# equilizerShield.net
KiCad netlist of a schematic drawn in EAGLE
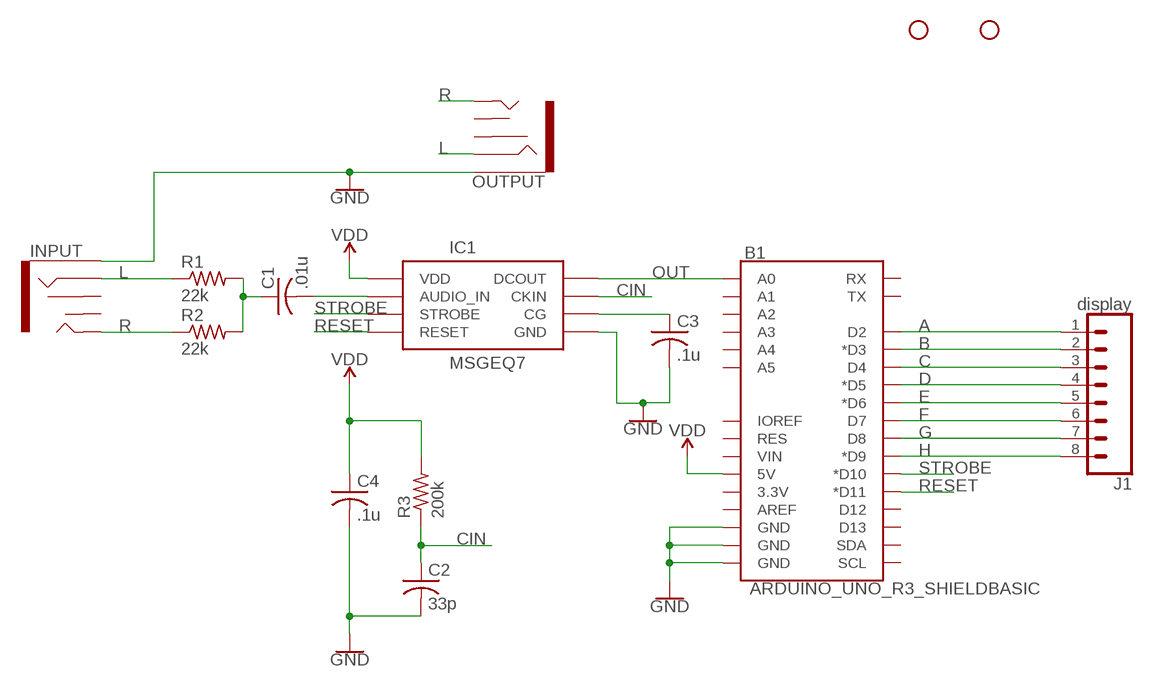
[diagram p0: schematic, sheet 1]

(export (version "E")
  (design (tool "Eeschema 10.0.6"))
  (components
    (comp (ref "B1")
      (value "ARDUINO_UNO_R3_SHIELDBASIC")
      (footprint "eagle-import:UNO_R3_SHIELD")
      (libsource (lib "eagle-import") (part "ARDUINO_UNO_R3_SHIELDBASIC"))
    )
    (comp (ref "C1")
      (value ".01u")
      (footprint "eagle-import:C0805")
      (libsource (lib "eagle-import") (part "C-USC0805"))
    )
    (comp (ref "C2")
      (value "33p")
      (footprint "eagle-import:C0805")
      (libsource (lib "eagle-import") (part "C-USC0805"))
    )
    (comp (ref "C3")
      (value ".1u")
      (footprint "eagle-import:C0805")
      (libsource (lib "eagle-import") (part "C-USC0805"))
    )
    (comp (ref "C4")
      (value ".1u")
      (footprint "eagle-import:C0805")
      (libsource (lib "eagle-import") (part "C-USC0805"))
    )
    (comp (ref "H1")
      (value "STAND-OFF")
      (footprint "eagle-import:STAND-OFF")
      (libsource (lib "eagle-import") (part "STAND-OFF"))
    )
    (comp (ref "H2")
      (value "STAND-OFF")
      (footprint "eagle-import:STAND-OFF")
      (libsource (lib "eagle-import") (part "STAND-OFF"))
    )
    (comp (ref "IC1")
      (value "MSGEQ7P")
      (footprint "eagle-import:DIP08")
      (libsource (lib "eagle-import") (part "MSGEQ7DIL"))
    )
    (comp (ref "INPUT")
      (value "AUDIO_JACK_3.5MM_PTH")
      (footprint "eagle-import:AUDIO-JACK")
      (libsource (lib "eagle-import") (part "AUDIO_JACK_3.5MM_PTH"))
    )
    (comp (ref "J1")
      (value "display")
      (footprint "eagle-import:1X08_LOCK")
      (libsource (lib "eagle-import") (part "CONN_08LOCK"))
    )
    (comp (ref "OUTPUT")
      (value "AUDIO_JACK_3.5MM_PTH")
      (footprint "eagle-import:AUDIO-JACK")
      (libsource (lib "eagle-import") (part "AUDIO_JACK_3.5MM_PTH"))
    )
    (comp (ref "R1")
      (value "22k")
      (footprint "eagle-import:R0805")
      (libsource (lib "eagle-import") (part "R-US_R0805"))
    )
    (comp (ref "R2")
      (value "22k")
      (footprint "eagle-import:R0805")
      (libsource (lib "eagle-import") (part "R-US_R0805"))
    )
    (comp (ref "R3")
      (value "200k")
      (footprint "eagle-import:R0805")
      (libsource (lib "eagle-import") (part "R-US_R0805"))
    )
  )
  (nets
    (net (code "1") (name "/A") (class "Default")
      (node (ref "B1") (pin "D2") (pinfunction "D2_D2") (pintype "bidirectional"))
      (node (ref "J1") (pin "1") (pinfunction "1_1") (pintype "passive"))
    )
    (net (code "2") (name "/B") (class "Default")
      (node (ref "B1") (pin "D3") (pinfunction "*D3_D3") (pintype "bidirectional"))
      (node (ref "J1") (pin "2") (pinfunction "2_2") (pintype "passive"))
    )
    (net (code "3") (name "/C") (class "Default")
      (node (ref "B1") (pin "D4") (pinfunction "D4_D4") (pintype "bidirectional"))
      (node (ref "J1") (pin "3") (pinfunction "3_3") (pintype "passive"))
    )
    (net (code "4") (name "/CIN") (class "Default")
      (node (ref "C2") (pin "1") (pinfunction "1_1") (pintype "passive"))
      (node (ref "IC1") (pin "8") (pinfunction "CKIN_8") (pintype "bidirectional"))
      (node (ref "R3") (pin "1") (pinfunction "1_1") (pintype "passive"))
    )
    (net (code "5") (name "/D") (class "Default")
      (node (ref "B1") (pin "D5") (pinfunction "*D5_D5") (pintype "bidirectional"))
      (node (ref "J1") (pin "4") (pinfunction "4_4") (pintype "passive"))
    )
    (net (code "6") (name "/E") (class "Default")
      (node (ref "B1") (pin "D6") (pinfunction "*D6_D6") (pintype "bidirectional"))
      (node (ref "J1") (pin "5") (pinfunction "5_5") (pintype "passive"))
    )
    (net (code "7") (name "/F") (class "Default")
      (node (ref "B1") (pin "D7") (pinfunction "D7_D7") (pintype "bidirectional"))
      (node (ref "J1") (pin "6") (pinfunction "6_6") (pintype "passive"))
    )
    (net (code "8") (name "/G") (class "Default")
      (node (ref "B1") (pin "D8") (pinfunction "D8_D8") (pintype "bidirectional"))
      (node (ref "J1") (pin "7") (pinfunction "7_7") (pintype "passive"))
    )
    (net (code "9") (name "/H") (class "Default")
      (node (ref "B1") (pin "D9") (pinfunction "*D9_D9") (pintype "bidirectional"))
      (node (ref "J1") (pin "8") (pinfunction "8_8") (pintype "passive"))
    )
    (net (code "10") (name "/L") (class "Default")
      (node (ref "INPUT") (pin "RING") (pinfunction "RING_RING") (pintype "bidirectional"))
      (node (ref "OUTPUT") (pin "RING") (pinfunction "RING_RING") (pintype "bidirectional"))
      (node (ref "R1") (pin "1") (pinfunction "1_1") (pintype "passive"))
    )
    (net (code "11") (name "/OUT") (class "Default")
      (node (ref "B1") (pin "A0") (pinfunction "A0_A0") (pintype "bidirectional"))
      (node (ref "IC1") (pin "3") (pinfunction "DCOUT_3") (pintype "bidirectional"))
    )
    (net (code "12") (name "/R") (class "Default")
      (node (ref "INPUT") (pin "TIP") (pinfunction "TIP_TIP") (pintype "bidirectional"))
      (node (ref "OUTPUT") (pin "TIP") (pinfunction "TIP_TIP") (pintype "bidirectional"))
      (node (ref "R2") (pin "1") (pinfunction "1_1") (pintype "passive"))
    )
    (net (code "13") (name "/RESET") (class "Default")
      (node (ref "B1") (pin "D11") (pinfunction "*D11_D11") (pintype "bidirectional"))
      (node (ref "IC1") (pin "7") (pinfunction "RESET_7") (pintype "input"))
    )
    (net (code "14") (name "/STROBE") (class "Default")
      (node (ref "B1") (pin "D10") (pinfunction "*D10_D10") (pintype "bidirectional"))
      (node (ref "IC1") (pin "4") (pinfunction "STROBE_4") (pintype "input"))
    )
    (net (code "15") (name "GND") (class "Default")
      (node (ref "B1") (pin "GND@0") (pinfunction "GND_GND@0") (pintype "bidirectional"))
      (node (ref "B1") (pin "GND@1") (pinfunction "GND_GND@1") (pintype "bidirectional"))
      (node (ref "B1") (pin "GND@2") (pinfunction "GND_GND@2") (pintype "bidirectional"))
      (node (ref "C2") (pin "2") (pinfunction "2_2") (pintype "passive"))
      (node (ref "C3") (pin "2") (pinfunction "2_2") (pintype "passive"))
      (node (ref "C4") (pin "2") (pinfunction "2_2") (pintype "passive"))
      (node (ref "IC1") (pin "2") (pinfunction "GND_2") (pintype "bidirectional"))
      (node (ref "INPUT") (pin "SLEEVE") (pinfunction "SLEEVE_SLEEVE") (pintype "bidirectional"))
      (node (ref "OUTPUT") (pin "SLEEVE") (pinfunction "SLEEVE_SLEEVE") (pintype "bidirectional"))
    )
    (net (code "16") (name "Net-(C1-Pad1)") (class "Default")
      (node (ref "C1") (pin "1") (pinfunction "1_1") (pintype "passive"))
      (node (ref "R1") (pin "2") (pinfunction "2_2") (pintype "passive"))
      (node (ref "R2") (pin "2") (pinfunction "2_2") (pintype "passive"))
    )
    (net (code "17") (name "Net-(IC1-AUDIO_IN)") (class "Default")
      (node (ref "C1") (pin "2") (pinfunction "2_2") (pintype "passive"))
      (node (ref "IC1") (pin "5") (pinfunction "AUDIO_IN_5") (pintype "input"))
    )
    (net (code "18") (name "Net-(IC1-CG)") (class "Default")
      (node (ref "C3") (pin "1") (pinfunction "1_1") (pintype "passive"))
      (node (ref "IC1") (pin "6") (pinfunction "CG_6") (pintype "bidirectional"))
    )
    (net (code "19") (name "VDD") (class "Default")
      (node (ref "B1") (pin "5V") (pinfunction "5V_5V") (pintype "bidirectional"))
      (node (ref "C4") (pin "1") (pinfunction "1_1") (pintype "passive"))
      (node (ref "IC1") (pin "1") (pinfunction "VDD_1") (pintype "input"))
      (node (ref "R3") (pin "2") (pinfunction "2_2") (pintype "passive"))
    )
    (net (code "20") (name "unconnected-(B1-Pad3.3V)") (class "Default")
      (node (ref "B1") (pin "3.3V") (pinfunction "3.3V_3.3V") (pintype "bidirectional"))
    )
    (net (code "21") (name "unconnected-(B1-PadA1)") (class "Default")
      (node (ref "B1") (pin "A1") (pinfunction "A1_A1") (pintype "bidirectional"))
    )
    (net (code "22") (name "unconnected-(B1-PadA2)") (class "Default")
      (node (ref "B1") (pin "A2") (pinfunction "A2_A2") (pintype "bidirectional"))
    )
    (net (code "23") (name "unconnected-(B1-PadA3)") (class "Default")
      (node (ref "B1") (pin "A3") (pinfunction "A3_A3") (pintype "bidirectional"))
    )
    (net (code "24") (name "unconnected-(B1-PadA4)") (class "Default")
      (node (ref "B1") (pin "A4") (pinfunction "A4_A4") (pintype "bidirectional"))
    )
    (net (code "25") (name "unconnected-(B1-PadA5)") (class "Default")
      (node (ref "B1") (pin "A5") (pinfunction "A5_A5") (pintype "bidirectional"))
    )
    (net (code "26") (name "unconnected-(B1-PadAREF)") (class "Default")
      (node (ref "B1") (pin "AREF") (pinfunction "AREF_AREF") (pintype "bidirectional"))
    )
    (net (code "27") (name "unconnected-(B1-PadD12)") (class "Default")
      (node (ref "B1") (pin "D12") (pinfunction "D12_D12") (pintype "bidirectional"))
    )
    (net (code "28") (name "unconnected-(B1-PadD13)") (class "Default")
      (node (ref "B1") (pin "D13") (pinfunction "D13_D13") (pintype "bidirectional"))
    )
    (net (code "29") (name "unconnected-(B1-PadIOREF)") (class "Default")
      (node (ref "B1") (pin "IOREF") (pinfunction "IOREF_IOREF") (pintype "bidirectional"))
    )
    (net (code "30") (name "unconnected-(B1-PadRES)") (class "Default")
      (node (ref "B1") (pin "RES") (pinfunction "RES_RES") (pintype "bidirectional"))
    )
    (net (code "31") (name "unconnected-(B1-PadRX)") (class "Default")
      (node (ref "B1") (pin "RX") (pinfunction "RX_RX") (pintype "bidirectional"))
    )
    (net (code "32") (name "unconnected-(B1-PadSCL)") (class "Default")
      (node (ref "B1") (pin "SCL") (pinfunction "SCL_SCL") (pintype "bidirectional"))
    )
    (net (code "33") (name "unconnected-(B1-PadSDA)") (class "Default")
      (node (ref "B1") (pin "SDA") (pinfunction "SDA_SDA") (pintype "bidirectional"))
    )
    (net (code "34") (name "unconnected-(B1-PadTX)") (class "Default")
      (node (ref "B1") (pin "TX") (pinfunction "TX_TX") (pintype "bidirectional"))
    )
    (net (code "35") (name "unconnected-(B1-PadVIN)") (class "Default")
      (node (ref "B1") (pin "VIN") (pinfunction "VIN_VIN") (pintype "bidirectional"))
    )
    (net (code "36") (name "unconnected-(INPUT-PadRSH)") (class "Default")
      (node (ref "INPUT") (pin "RSH") (pinfunction "RSH_RSH") (pintype "bidirectional"))
    )
    (net (code "37") (name "unconnected-(INPUT-PadTSH)") (class "Default")
      (node (ref "INPUT") (pin "TSH") (pinfunction "TSH_TSH") (pintype "bidirectional"))
    )
    (net (code "38") (name "unconnected-(OUTPUT-PadRSH)") (class "Default")
      (node (ref "OUTPUT") (pin "RSH") (pinfunction "RSH_RSH") (pintype "bidirectional"))
    )
    (net (code "39") (name "unconnected-(OUTPUT-PadTSH)") (class "Default")
      (node (ref "OUTPUT") (pin "TSH") (pinfunction "TSH_TSH") (pintype "bidirectional"))
    )
  )
)
